# input.net
KiCad netlist of a schematic drawn in Altium Designer
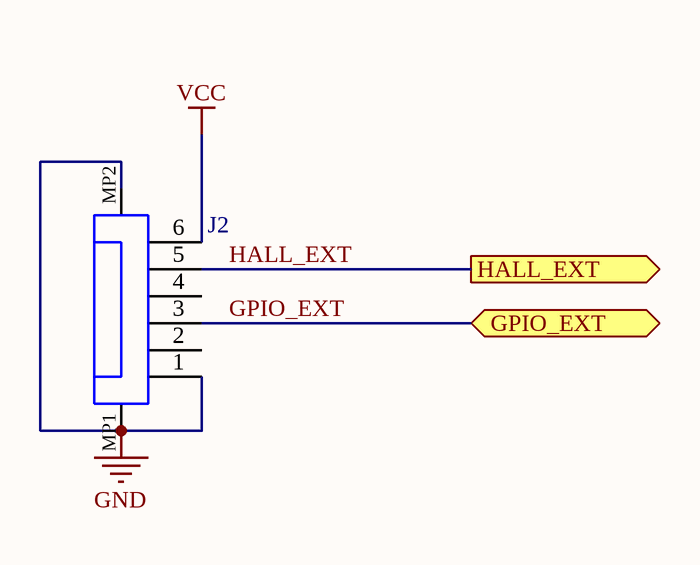
[diagram p0: input.SchDoc]

(export (version "E")
  (design (tool "Eeschema 10.0.6"))
  (components
    (comp (ref "J2")
      (value "68610614422")
      (footprint "68610614422")
      (description "SMT ZIF Connectors WR-FPC, Horizontal, Bottom Contact, pitch 1 mm, 6 pins")
      (fields (field (name "MANUFACTURER") "Wurth Elektronik") (field (name "PUBLISHER") "WurthElektronik"))
      (libsource (lib "Altium Content Vault") (part "WE-68X1061XXX22-6"))
    )
  )
  (nets
    (net (code "1") (name "/GPIO_EXT") (class "Default")
      (node (ref "J2") (pin "3") (pinfunction "3_3") (pintype "passive"))
    )
    (net (code "2") (name "/HALL_EXT") (class "Default")
      (node (ref "J2") (pin "5") (pinfunction "5_5") (pintype "passive"))
    )
    (net (code "3") (name "GND") (class "Default")
      (node (ref "J2") (pin "1") (pinfunction "1_1") (pintype "passive"))
      (node (ref "J2") (pin "MP1") (pinfunction "MP1_MP1") (pintype "passive"))
      (node (ref "J2") (pin "MP2") (pinfunction "MP2_MP2") (pintype "passive"))
    )
    (net (code "4") (name "VCC") (class "Default")
      (node (ref "J2") (pin "6") (pinfunction "6_6") (pintype "passive"))
    )
    (net (code "5") (name "unconnected-(J2-Pad2)") (class "Default")
      (node (ref "J2") (pin "2") (pinfunction "2_2") (pintype "passive"))
    )
    (net (code "6") (name "unconnected-(J2-Pad4)") (class "Default")
      (node (ref "J2") (pin "4") (pinfunction "4_4") (pintype "passive"))
    )
  )
)
